# motor_driver.net
KiCad netlist of a schematic drawn in EAGLE
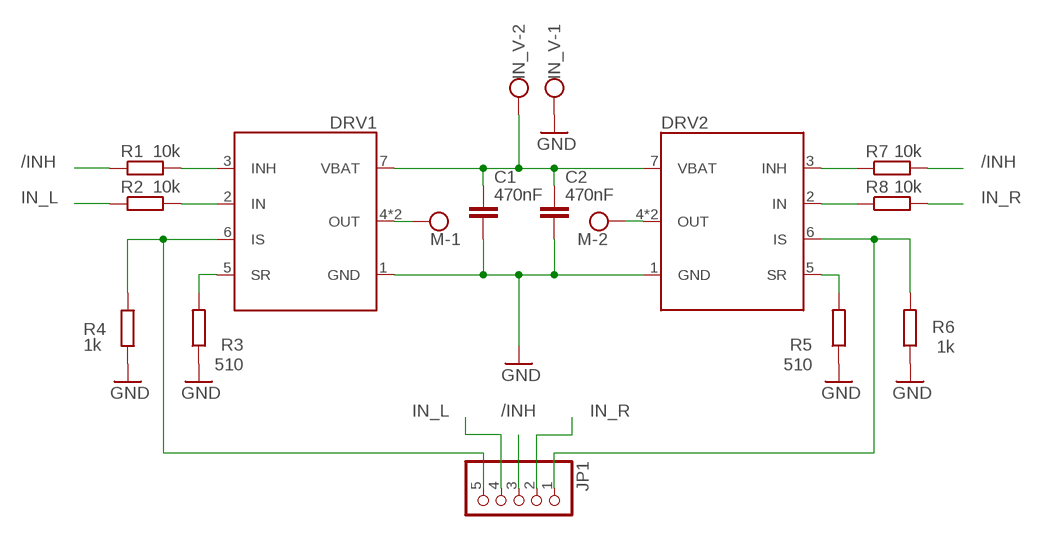
[diagram p0: schematic, sheet 1]

(export (version "E")
  (design (tool "Eeschema 10.0.6"))
  (components
    (comp (ref "C1")
      (value "470nF")
      (footprint "eagle-import:C0805")
      (libsource (lib "eagle-import") (part "C-EUC0805"))
    )
    (comp (ref "C2")
      (value "470nF")
      (footprint "eagle-import:C0805")
      (libsource (lib "eagle-import") (part "C-EUC0805"))
    )
    (comp (ref "DRV1")
      (value "FAN7093_F085SMD")
      (footprint "eagle-import:TO-263-8")
      (libsource (lib "eagle-import") (part "FAN7093_F085SMD"))
    )
    (comp (ref "DRV2")
      (value "FAN7093_F085SMD")
      (footprint "eagle-import:TO-263-8")
      (libsource (lib "eagle-import") (part "FAN7093_F085SMD"))
    )
    (comp (ref "IN_V")
      (value "W237-102")
      (footprint "eagle-import:W237-102")
      (fields (field (name "MPN") "237-102"))
      (libsource (lib "eagle-import") (part "W237-102"))
    )
    (comp (ref "JP1")
      (value "PINHD-1X5")
      (footprint "eagle-import:1X05")
      (libsource (lib "eagle-import") (part "PINHD-1X5"))
    )
    (comp (ref "M")
      (value "W237-102")
      (footprint "eagle-import:W237-102")
      (fields (field (name "MPN") "237-102"))
      (libsource (lib "eagle-import") (part "W237-102"))
    )
    (comp (ref "R1")
      (value "10k")
      (footprint "eagle-import:R0805")
      (libsource (lib "eagle-import") (part "R-EU_R0805"))
    )
    (comp (ref "R2")
      (value "10k")
      (footprint "eagle-import:R0805")
      (libsource (lib "eagle-import") (part "R-EU_R0805"))
    )
    (comp (ref "R3")
      (value "510")
      (footprint "eagle-import:R0805")
      (libsource (lib "eagle-import") (part "R-EU_R0805"))
    )
    (comp (ref "R4")
      (value "1k")
      (footprint "eagle-import:R0805")
      (libsource (lib "eagle-import") (part "R-EU_R0805"))
    )
    (comp (ref "R5")
      (value "510")
      (footprint "eagle-import:R0805")
      (libsource (lib "eagle-import") (part "R-EU_R0805"))
    )
    (comp (ref "R6")
      (value "1k")
      (footprint "eagle-import:R0805")
      (libsource (lib "eagle-import") (part "R-EU_R0805"))
    )
    (comp (ref "R7")
      (value "10k")
      (footprint "eagle-import:R0805")
      (libsource (lib "eagle-import") (part "R-EU_R0805"))
    )
    (comp (ref "R8")
      (value "10k")
      (footprint "eagle-import:R0805")
      (libsource (lib "eagle-import") (part "R-EU_R0805"))
    )
  )
  (nets
    (net (code "1") (name "/IN_L") (class "Default")
      (node (ref "JP1") (pin "4") (pinfunction "4_4") (pintype "passive"))
      (node (ref "R2") (pin "1") (pinfunction "1_1") (pintype "passive"))
    )
    (net (code "2") (name "/IN_R") (class "Default")
      (node (ref "JP1") (pin "2") (pinfunction "2_2") (pintype "passive"))
      (node (ref "R8") (pin "2") (pinfunction "2_2") (pintype "passive"))
    )
    (net (code "3") (name "/{slash}INH") (class "Default")
      (node (ref "JP1") (pin "3") (pinfunction "3_3") (pintype "passive"))
      (node (ref "R1") (pin "1") (pinfunction "1_1") (pintype "passive"))
      (node (ref "R7") (pin "2") (pinfunction "2_2") (pintype "passive"))
    )
    (net (code "4") (name "GND") (class "Default")
      (node (ref "C1") (pin "2") (pinfunction "2_2") (pintype "passive"))
      (node (ref "C2") (pin "2") (pinfunction "2_2") (pintype "passive"))
      (node (ref "DRV1") (pin "1") (pinfunction "GND_1") (pintype "bidirectional"))
      (node (ref "DRV2") (pin "1") (pinfunction "GND_1") (pintype "bidirectional"))
      (node (ref "IN_V") (pin "1") (pinfunction "KL_1") (pintype "passive"))
      (node (ref "R3") (pin "1") (pinfunction "1_1") (pintype "passive"))
      (node (ref "R4") (pin "2") (pinfunction "2_2") (pintype "passive"))
      (node (ref "R5") (pin "1") (pinfunction "1_1") (pintype "passive"))
      (node (ref "R6") (pin "1") (pinfunction "1_1") (pintype "passive"))
    )
    (net (code "5") (name "Net-(DRV1-IN)") (class "Default")
      (node (ref "DRV1") (pin "2") (pinfunction "IN_2") (pintype "bidirectional"))
      (node (ref "R2") (pin "2") (pinfunction "2_2") (pintype "passive"))
    )
    (net (code "6") (name "Net-(DRV1-INH)") (class "Default")
      (node (ref "DRV1") (pin "3") (pinfunction "INH_3") (pintype "bidirectional"))
      (node (ref "R1") (pin "2") (pinfunction "2_2") (pintype "passive"))
    )
    (net (code "7") (name "Net-(DRV1-IS)") (class "Default")
      (node (ref "DRV1") (pin "6") (pinfunction "IS_6") (pintype "bidirectional"))
      (node (ref "JP1") (pin "5") (pinfunction "5_5") (pintype "passive"))
      (node (ref "R4") (pin "1") (pinfunction "1_1") (pintype "passive"))
    )
    (net (code "8") (name "Net-(DRV1-SR)") (class "Default")
      (node (ref "DRV1") (pin "5") (pinfunction "SR_5") (pintype "bidirectional"))
      (node (ref "R3") (pin "2") (pinfunction "2_2") (pintype "passive"))
    )
    (net (code "9") (name "Net-(DRV1-VBAT)") (class "Default")
      (node (ref "C1") (pin "1") (pinfunction "1_1") (pintype "passive"))
      (node (ref "C2") (pin "1") (pinfunction "1_1") (pintype "passive"))
      (node (ref "DRV1") (pin "7") (pinfunction "VBAT_7") (pintype "bidirectional"))
      (node (ref "DRV2") (pin "7") (pinfunction "VBAT_7") (pintype "bidirectional"))
      (node (ref "IN_V") (pin "2") (pinfunction "KL_2") (pintype "passive"))
    )
    (net (code "10") (name "Net-(DRV2-IN)") (class "Default")
      (node (ref "DRV2") (pin "2") (pinfunction "IN_2") (pintype "bidirectional"))
      (node (ref "R8") (pin "1") (pinfunction "1_1") (pintype "passive"))
    )
    (net (code "11") (name "Net-(DRV2-INH)") (class "Default")
      (node (ref "DRV2") (pin "3") (pinfunction "INH_3") (pintype "bidirectional"))
      (node (ref "R7") (pin "1") (pinfunction "1_1") (pintype "passive"))
    )
    (net (code "12") (name "Net-(DRV2-IS)") (class "Default")
      (node (ref "DRV2") (pin "6") (pinfunction "IS_6") (pintype "bidirectional"))
      (node (ref "JP1") (pin "1") (pinfunction "1_1") (pintype "passive"))
      (node (ref "R6") (pin "2") (pinfunction "2_2") (pintype "passive"))
    )
    (net (code "13") (name "Net-(DRV2-SR)") (class "Default")
      (node (ref "DRV2") (pin "5") (pinfunction "SR_5") (pintype "bidirectional"))
      (node (ref "R5") (pin "2") (pinfunction "2_2") (pintype "passive"))
    )
    (net (code "14") (name "Net-(MA-KL)") (class "Default")
      (node (ref "DRV1") (pin "4") (pinfunction "OUT_4") (pintype "bidirectional"))
      (node (ref "DRV1") (pin "8") (pinfunction "OUT_8") (pintype "bidirectional"))
      (node (ref "M") (pin "1") (pinfunction "KL_1") (pintype "passive"))
    )
    (net (code "15") (name "Net-(MB-KL)") (class "Default")
      (node (ref "DRV2") (pin "4") (pinfunction "OUT_4") (pintype "bidirectional"))
      (node (ref "DRV2") (pin "8") (pinfunction "OUT_8") (pintype "bidirectional"))
      (node (ref "M") (pin "2") (pinfunction "KL_2") (pintype "passive"))
    )
  )
)
